# Qbot2.net
KiCad netlist of a schematic drawn in Altium Designer
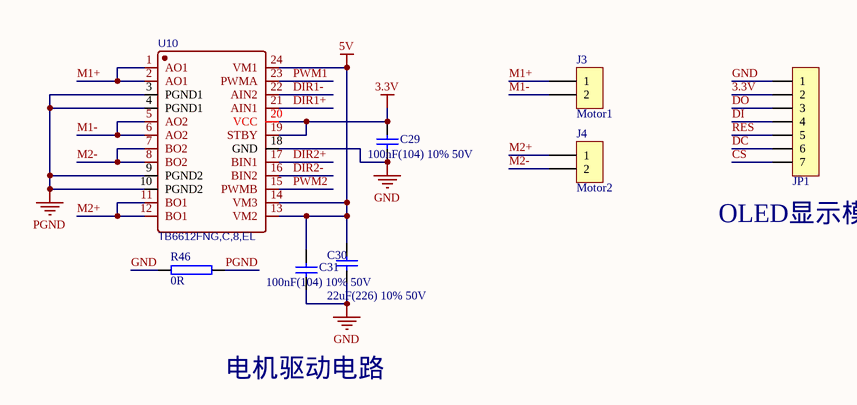
[diagram p0: Qbot2.SchDoc]

(export (version "E")
  (design (tool "Eeschema 10.0.6"))
  (components
    (comp (ref "C29")
      (value "100nF(104) 10% 50V")
      (footprint "LC-0805_C")
      (description "贴片电容")
      (libsource (lib "Miscellaneous Devices LC") (part "0805 100nF(104) 10% 50V"))
    )
    (comp (ref "C30")
      (value "22uF(226) 10% 50V")
      (footprint "CD B(3528)")
      (description "贴片电容")
      (libsource (lib "Miscellaneous Devices LC") (part "0805 100nF(104) 10% 50V"))
    )
    (comp (ref "C31")
      (value "100nF(104) 10% 50V")
      (footprint "LC-0805_C")
      (description "贴片电容")
      (libsource (lib "Miscellaneous Devices LC") (part "0805 100nF(104) 10% 50V"))
    )
    (comp (ref "J3")
      (value "Motor1")
      (footprint "CONN-TH_1.25T-2A_1.25T-2A")
      (description "jointbar")
      (libsource (lib "接口与插座") (part "SIP2"))
    )
    (comp (ref "J4")
      (value "Motor2")
      (footprint "CONN-TH_1.25T-2A_1.25T-2A")
      (description "jointbar")
      (libsource (lib "接口与插座") (part "SIP2"))
    )
    (comp (ref "JP1")
      (value "HDR-1X7")
      (footprint "HDR2.54-M-LI-7P")
      (description "7P接插件")
      (fields (field (name "版权归属") "源创客"))
      (libsource (lib "4.2   - 接插件-脚距1.25") (part "Header 7"))
    )
    (comp (ref "R46") (value "0R") (footprint "LC-0805_R") (libsource (lib "*") (part "RES")))
    (comp (ref "U10")
      (value "TB6612FNG,C,8,EL")
      (footprint "SSOP24")
      (fields (field (name "BOM_SUPPLIER PART") "C141517") (field (name "CONTRIBUTOR") "LCSC"))
      (libsource (lib "Qbot") (part "TB6612FNG,C,8,EL"))
    )
  )
  (nets
    (net (code "1") (name "/CS") (class "Default")
      (node (ref "JP1") (pin "7") (pinfunction "7_7") (pintype "passive"))
    )
    (net (code "2") (name "/DC") (class "Default")
      (node (ref "JP1") (pin "6") (pinfunction "6_6") (pintype "passive"))
    )
    (net (code "3") (name "/DI") (class "Default")
      (node (ref "JP1") (pin "4") (pinfunction "4_4") (pintype "passive"))
    )
    (net (code "4") (name "/DIR1+") (class "Default")
      (node (ref "U10") (pin "21") (pinfunction "AIN1_21") (pintype "passive"))
    )
    (net (code "5") (name "/DIR1-") (class "Default")
      (node (ref "U10") (pin "22") (pinfunction "AIN2_22") (pintype "passive"))
    )
    (net (code "6") (name "/DIR2+") (class "Default")
      (node (ref "U10") (pin "17") (pinfunction "BIN1_17") (pintype "passive"))
    )
    (net (code "7") (name "/DIR2-") (class "Default")
      (node (ref "U10") (pin "16") (pinfunction "BIN2_16") (pintype "passive"))
    )
    (net (code "8") (name "/DO") (class "Default")
      (node (ref "JP1") (pin "3") (pinfunction "3_3") (pintype "passive"))
    )
    (net (code "9") (name "/M1+") (class "Default")
      (node (ref "J3") (pin "1") (pinfunction "1_1") (pintype "passive"))
      (node (ref "U10") (pin "1") (pinfunction "AO1_1") (pintype "passive"))
      (node (ref "U10") (pin "2") (pinfunction "AO1_2") (pintype "passive"))
    )
    (net (code "10") (name "/M1-") (class "Default")
      (node (ref "J3") (pin "2") (pinfunction "2_2") (pintype "passive"))
      (node (ref "U10") (pin "5") (pinfunction "AO2_5") (pintype "passive"))
      (node (ref "U10") (pin "6") (pinfunction "AO2_6") (pintype "passive"))
    )
    (net (code "11") (name "/M2+") (class "Default")
      (node (ref "J4") (pin "1") (pinfunction "1_1") (pintype "passive"))
      (node (ref "U10") (pin "11") (pinfunction "BO1_11") (pintype "passive"))
      (node (ref "U10") (pin "12") (pinfunction "BO1_12") (pintype "passive"))
    )
    (net (code "12") (name "/M2-") (class "Default")
      (node (ref "J4") (pin "2") (pinfunction "2_2") (pintype "passive"))
      (node (ref "U10") (pin "7") (pinfunction "BO2_7") (pintype "passive"))
      (node (ref "U10") (pin "8") (pinfunction "BO2_8") (pintype "passive"))
    )
    (net (code "13") (name "/PWM1") (class "Default")
      (node (ref "U10") (pin "23") (pinfunction "PWMA_23") (pintype "passive"))
    )
    (net (code "14") (name "/PWM2") (class "Default")
      (node (ref "U10") (pin "15") (pinfunction "PWMB_15") (pintype "passive"))
    )
    (net (code "15") (name "/RES") (class "Default")
      (node (ref "JP1") (pin "5") (pinfunction "5_5") (pintype "passive"))
    )
    (net (code "16") (name "3.3V") (class "Default")
      (node (ref "C29") (pin "2") (pinfunction "2_2") (pintype "passive"))
      (node (ref "JP1") (pin "2") (pinfunction "2_2") (pintype "passive"))
      (node (ref "U10") (pin "19") (pinfunction "STBY_19") (pintype "passive"))
      (node (ref "U10") (pin "20") (pinfunction "VCC_20") (pintype "passive"))
    )
    (net (code "17") (name "5V") (class "Default")
      (node (ref "C30") (pin "2") (pinfunction "2_2") (pintype "passive"))
      (node (ref "C31") (pin "2") (pinfunction "2_2") (pintype "passive"))
      (node (ref "U10") (pin "13") (pinfunction "VM2_13") (pintype "passive"))
      (node (ref "U10") (pin "14") (pinfunction "VM3_14") (pintype "passive"))
      (node (ref "U10") (pin "24") (pinfunction "VM1_24") (pintype "passive"))
    )
    (net (code "18") (name "GND") (class "Default")
      (node (ref "C29") (pin "1") (pinfunction "1_1") (pintype "passive"))
      (node (ref "C30") (pin "1") (pinfunction "1_1") (pintype "passive"))
      (node (ref "C31") (pin "1") (pinfunction "1_1") (pintype "passive"))
      (node (ref "JP1") (pin "1") (pinfunction "1_1") (pintype "passive"))
      (node (ref "R46") (pin "1") (pinfunction "1_1") (pintype "passive"))
      (node (ref "U10") (pin "18") (pinfunction "GND_18") (pintype "passive"))
    )
    (net (code "19") (name "PGND") (class "Default")
      (node (ref "R46") (pin "2") (pinfunction "2_2") (pintype "passive"))
      (node (ref "U10") (pin "10") (pinfunction "PGND2_10") (pintype "passive"))
      (node (ref "U10") (pin "3") (pinfunction "PGND1_3") (pintype "passive"))
      (node (ref "U10") (pin "4") (pinfunction "PGND1_4") (pintype "passive"))
      (node (ref "U10") (pin "9") (pinfunction "PGND2_9") (pintype "passive"))
    )
  )
)
